# Digital__IO.net
KiCad netlist of a schematic drawn in Altium Designer
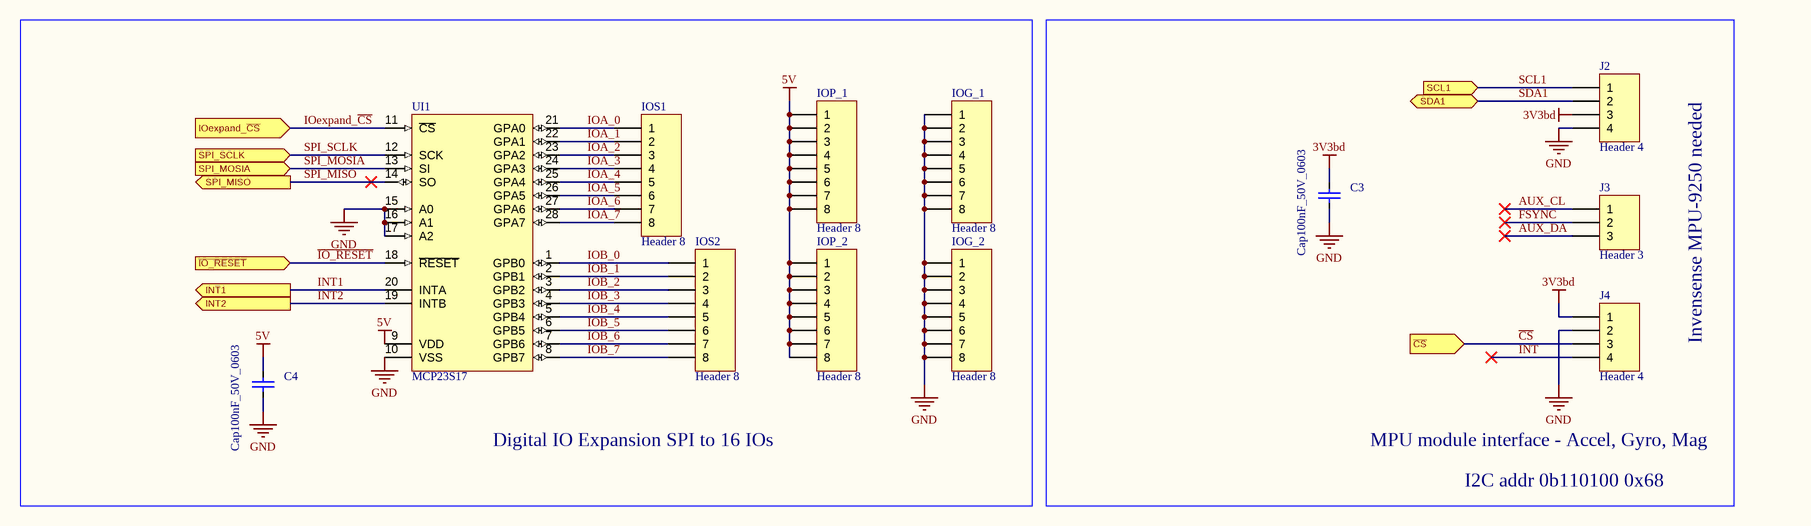
[diagram p0: Digital_ IO.SchDoc]

(export (version "E")
  (design (tool "Eeschema 10.0.6"))
  (components
    (comp (ref "C3")
      (value "Cap100nF_50V_0603")
      (footprint "0603C_L")
      (libsource (lib "Advanced] Training Course - A365") (part "CAP General"))
    )
    (comp (ref "C4")
      (value "Cap100nF_50V_0603")
      (footprint "0603C_L")
      (libsource (lib "Advanced] Training Course - A365") (part "CAP General"))
    )
    (comp (ref "IOG_1")
      (value "Header 8")
      (footprint "HDR1X8")
      (description "Header, 8-Pin")
      (fields (field (name "PUBLISHER") "Altium Limited"))
      (libsource (lib "Advanced] Training Course - A365") (part "Header 8"))
    )
    (comp (ref "IOG_2")
      (value "Header 8")
      (footprint "HDR1X8")
      (description "Header, 8-Pin")
      (fields (field (name "PUBLISHER") "Altium Limited"))
      (libsource (lib "Advanced] Training Course - A365") (part "Header 8"))
    )
    (comp (ref "IOP_1")
      (value "Header 8")
      (footprint "HDR1X8")
      (description "Header, 8-Pin")
      (fields (field (name "PUBLISHER") "Altium Limited"))
      (libsource (lib "Advanced] Training Course - A365") (part "Header 8"))
    )
    (comp (ref "IOP_2")
      (value "Header 8")
      (footprint "HDR1X8")
      (description "Header, 8-Pin")
      (fields (field (name "PUBLISHER") "Altium Limited"))
      (libsource (lib "Advanced] Training Course - A365") (part "Header 8"))
    )
    (comp (ref "IOS1")
      (value "Header 8")
      (footprint "HDR1X8")
      (description "Header, 8-Pin")
      (fields (field (name "PUBLISHER") "Altium Limited"))
      (libsource (lib "Advanced] Training Course - A365") (part "Header 8"))
    )
    (comp (ref "IOS2")
      (value "Header 8")
      (footprint "HDR1X8")
      (description "Header, 8-Pin")
      (fields (field (name "PUBLISHER") "Altium Limited"))
      (libsource (lib "Advanced] Training Course - A365") (part "Header 8"))
    )
    (comp (ref "J2")
      (value "Header 4")
      (footprint "HDR1X4")
      (description "Header, 4-Pin")
      (fields (field (name "PUBLISHER") "Altium Limited"))
      (libsource (lib "Advanced] Training Course - A365") (part "Header 4"))
    )
    (comp (ref "J3")
      (value "Header 3")
      (footprint "HDR1X3")
      (description "Header, 3-Pin")
      (fields (field (name "PUBLISHER") "Altium Limited"))
      (libsource (lib "Advanced] Training Course - A365") (part "Header 3"))
    )
    (comp (ref "J4")
      (value "Header 4")
      (footprint "HDR1X4")
      (description "Header, 4-Pin")
      (fields (field (name "PUBLISHER") "Altium Limited"))
      (libsource (lib "Advanced] Training Course - A365") (part "Header 4"))
    )
    (comp (ref "UI1")
      (value "MCP23S17")
      (footprint "SOIC-SO28_L")
      (description "16-Bit I/O Expander with Serial Interface, 28-Pin SOIC, Extended Temperature, Tape and Reel")
      (fields
        (field (name "MANUFACTURER") "Microchip")
        (field (name "MANUFACTURER PART NUMBER") "MCP23S17T-E/SO")
        (field (name "AVAILABLE PREVIEW IMAGES") "2D")
      )
      (libsource (lib "Advanced] Training Course - A365") (part "MCP23S17"))
    )
  )
  (nets
    (net (code "1") (name "/AUX_CL") (class "Default")
      (node (ref "J3") (pin "1") (pinfunction "1_1") (pintype "passive+no_connect"))
    )
    (net (code "2") (name "/AUX_DA") (class "Default")
      (node (ref "J3") (pin "3") (pinfunction "3_3") (pintype "passive+no_connect"))
    )
    (net (code "3") (name "/FSYNC") (class "Default")
      (node (ref "J3") (pin "2") (pinfunction "2_2") (pintype "passive+no_connect"))
    )
    (net (code "4") (name "/INT") (class "Default")
      (node (ref "J4") (pin "4") (pinfunction "4_4") (pintype "passive+no_connect"))
    )
    (net (code "5") (name "/INT1") (class "Default")
      (node (ref "UI1") (pin "20") (pinfunction "INTA_20") (pintype "open_collector"))
    )
    (net (code "6") (name "/INT2") (class "Default")
      (node (ref "UI1") (pin "19") (pinfunction "INTB_19") (pintype "open_collector"))
    )
    (net (code "7") (name "/IOA_0") (class "Default")
      (node (ref "IOS1") (pin "1") (pinfunction "1_1") (pintype "passive"))
      (node (ref "UI1") (pin "21") (pinfunction "GPA0_21") (pintype "bidirectional"))
    )
    (net (code "8") (name "/IOA_1") (class "Default")
      (node (ref "IOS1") (pin "2") (pinfunction "2_2") (pintype "passive"))
      (node (ref "UI1") (pin "22") (pinfunction "GPA1_22") (pintype "bidirectional"))
    )
    (net (code "9") (name "/IOA_2") (class "Default")
      (node (ref "IOS1") (pin "3") (pinfunction "3_3") (pintype "passive"))
      (node (ref "UI1") (pin "23") (pinfunction "GPA2_23") (pintype "bidirectional"))
    )
    (net (code "10") (name "/IOA_3") (class "Default")
      (node (ref "IOS1") (pin "4") (pinfunction "4_4") (pintype "passive"))
      (node (ref "UI1") (pin "24") (pinfunction "GPA3_24") (pintype "bidirectional"))
    )
    (net (code "11") (name "/IOA_4") (class "Default")
      (node (ref "IOS1") (pin "5") (pinfunction "5_5") (pintype "passive"))
      (node (ref "UI1") (pin "25") (pinfunction "GPA4_25") (pintype "bidirectional"))
    )
    (net (code "12") (name "/IOA_5") (class "Default")
      (node (ref "IOS1") (pin "6") (pinfunction "6_6") (pintype "passive"))
      (node (ref "UI1") (pin "26") (pinfunction "GPA5_26") (pintype "bidirectional"))
    )
    (net (code "13") (name "/IOA_6") (class "Default")
      (node (ref "IOS1") (pin "7") (pinfunction "7_7") (pintype "passive"))
      (node (ref "UI1") (pin "27") (pinfunction "GPA6_27") (pintype "bidirectional"))
    )
    (net (code "14") (name "/IOA_7") (class "Default")
      (node (ref "IOS1") (pin "8") (pinfunction "8_8") (pintype "passive"))
      (node (ref "UI1") (pin "28") (pinfunction "GPA7_28") (pintype "bidirectional"))
    )
    (net (code "15") (name "/IOB_0") (class "Default")
      (node (ref "IOS2") (pin "1") (pinfunction "1_1") (pintype "passive"))
      (node (ref "UI1") (pin "1") (pinfunction "GPB0_1") (pintype "bidirectional"))
    )
    (net (code "16") (name "/IOB_1") (class "Default")
      (node (ref "IOS2") (pin "2") (pinfunction "2_2") (pintype "passive"))
      (node (ref "UI1") (pin "2") (pinfunction "GPB1_2") (pintype "bidirectional"))
    )
    (net (code "17") (name "/IOB_2") (class "Default")
      (node (ref "IOS2") (pin "3") (pinfunction "3_3") (pintype "passive"))
      (node (ref "UI1") (pin "3") (pinfunction "GPB2_3") (pintype "bidirectional"))
    )
    (net (code "18") (name "/IOB_3") (class "Default")
      (node (ref "IOS2") (pin "4") (pinfunction "4_4") (pintype "passive"))
      (node (ref "UI1") (pin "4") (pinfunction "GPB3_4") (pintype "bidirectional"))
    )
    (net (code "19") (name "/IOB_4") (class "Default")
      (node (ref "IOS2") (pin "5") (pinfunction "5_5") (pintype "passive"))
      (node (ref "UI1") (pin "5") (pinfunction "GPB4_5") (pintype "bidirectional"))
    )
    (net (code "20") (name "/IOB_5") (class "Default")
      (node (ref "IOS2") (pin "6") (pinfunction "6_6") (pintype "passive"))
      (node (ref "UI1") (pin "6") (pinfunction "GPB5_6") (pintype "bidirectional"))
    )
    (net (code "21") (name "/IOB_6") (class "Default")
      (node (ref "IOS2") (pin "7") (pinfunction "7_7") (pintype "passive"))
      (node (ref "UI1") (pin "7") (pinfunction "GPB6_7") (pintype "bidirectional"))
    )
    (net (code "22") (name "/IOB_7") (class "Default")
      (node (ref "IOS2") (pin "8") (pinfunction "8_8") (pintype "passive"))
      (node (ref "UI1") (pin "8") (pinfunction "GPB7_8") (pintype "bidirectional"))
    )
    (net (code "23") (name "/IO_RESET") (class "Default")
      (node (ref "UI1") (pin "18") (pinfunction "~{RESET}_18") (pintype "input"))
    )
    (net (code "24") (name "/IOexpand_~{CS}") (class "Default")
      (node (ref "UI1") (pin "11") (pinfunction "~{CS}_11") (pintype "input"))
    )
    (net (code "25") (name "/SCL1") (class "Default")
      (node (ref "J2") (pin "1") (pinfunction "1_1") (pintype "passive"))
    )
    (net (code "26") (name "/SDA1") (class "Default")
      (node (ref "J2") (pin "2") (pinfunction "2_2") (pintype "passive"))
    )
    (net (code "27") (name "/SPI_MISO") (class "Default")
      (node (ref "UI1") (pin "14") (pinfunction "SO_14") (pintype "bidirectional"))
    )
    (net (code "28") (name "/SPI_MOSIA") (class "Default")
      (node (ref "UI1") (pin "13") (pinfunction "SI_13") (pintype "input"))
    )
    (net (code "29") (name "/SPI_SCLK") (class "Default")
      (node (ref "UI1") (pin "12") (pinfunction "SCK_12") (pintype "input"))
    )
    (net (code "30") (name "/~{CS}") (class "Default")
      (node (ref "J4") (pin "3") (pinfunction "3_3") (pintype "passive"))
    )
    (net (code "31") (name "3V3bd") (class "Default")
      (node (ref "C3") (pin "2") (pinfunction "2_2") (pintype "passive"))
      (node (ref "J2") (pin "3") (pinfunction "3_3") (pintype "passive"))
      (node (ref "J4") (pin "1") (pinfunction "1_1") (pintype "passive"))
    )
    (net (code "32") (name "5V") (class "Default")
      (node (ref "C4") (pin "2") (pinfunction "2_2") (pintype "passive"))
      (node (ref "IOP_1") (pin "1") (pinfunction "1_1") (pintype "passive"))
      (node (ref "IOP_1") (pin "2") (pinfunction "2_2") (pintype "passive"))
      (node (ref "IOP_1") (pin "3") (pinfunction "3_3") (pintype "passive"))
      (node (ref "IOP_1") (pin "4") (pinfunction "4_4") (pintype "passive"))
      (node (ref "IOP_1") (pin "5") (pinfunction "5_5") (pintype "passive"))
      (node (ref "IOP_1") (pin "6") (pinfunction "6_6") (pintype "passive"))
      (node (ref "IOP_1") (pin "7") (pinfunction "7_7") (pintype "passive"))
      (node (ref "IOP_1") (pin "8") (pinfunction "8_8") (pintype "passive"))
      (node (ref "IOP_2") (pin "1") (pinfunction "1_1") (pintype "passive"))
      (node (ref "IOP_2") (pin "2") (pinfunction "2_2") (pintype "passive"))
      (node (ref "IOP_2") (pin "3") (pinfunction "3_3") (pintype "passive"))
      (node (ref "IOP_2") (pin "4") (pinfunction "4_4") (pintype "passive"))
      (node (ref "IOP_2") (pin "5") (pinfunction "5_5") (pintype "passive"))
      (node (ref "IOP_2") (pin "6") (pinfunction "6_6") (pintype "passive"))
      (node (ref "IOP_2") (pin "7") (pinfunction "7_7") (pintype "passive"))
      (node (ref "IOP_2") (pin "8") (pinfunction "8_8") (pintype "passive"))
      (node (ref "UI1") (pin "9") (pinfunction "VDD_9") (pintype "power_in"))
    )
    (net (code "33") (name "GND") (class "Default")
      (node (ref "C3") (pin "1") (pinfunction "1_1") (pintype "passive"))
      (node (ref "C4") (pin "1") (pinfunction "1_1") (pintype "passive"))
      (node (ref "IOG_1") (pin "1") (pinfunction "1_1") (pintype "passive"))
      (node (ref "IOG_1") (pin "2") (pinfunction "2_2") (pintype "passive"))
      (node (ref "IOG_1") (pin "3") (pinfunction "3_3") (pintype "passive"))
      (node (ref "IOG_1") (pin "4") (pinfunction "4_4") (pintype "passive"))
      (node (ref "IOG_1") (pin "5") (pinfunction "5_5") (pintype "passive"))
      (node (ref "IOG_1") (pin "6") (pinfunction "6_6") (pintype "passive"))
      (node (ref "IOG_1") (pin "7") (pinfunction "7_7") (pintype "passive"))
      (node (ref "IOG_1") (pin "8") (pinfunction "8_8") (pintype "passive"))
      (node (ref "IOG_2") (pin "1") (pinfunction "1_1") (pintype "passive"))
      (node (ref "IOG_2") (pin "2") (pinfunction "2_2") (pintype "passive"))
      (node (ref "IOG_2") (pin "3") (pinfunction "3_3") (pintype "passive"))
      (node (ref "IOG_2") (pin "4") (pinfunction "4_4") (pintype "passive"))
      (node (ref "IOG_2") (pin "5") (pinfunction "5_5") (pintype "passive"))
      (node (ref "IOG_2") (pin "6") (pinfunction "6_6") (pintype "passive"))
      (node (ref "IOG_2") (pin "7") (pinfunction "7_7") (pintype "passive"))
      (node (ref "IOG_2") (pin "8") (pinfunction "8_8") (pintype "passive"))
      (node (ref "J2") (pin "4") (pinfunction "4_4") (pintype "passive"))
      (node (ref "J4") (pin "2") (pinfunction "2_2") (pintype "passive"))
      (node (ref "UI1") (pin "10") (pinfunction "VSS_10") (pintype "power_in"))
      (node (ref "UI1") (pin "15") (pinfunction "A0_15") (pintype "input"))
      (node (ref "UI1") (pin "16") (pinfunction "A1_16") (pintype "input"))
      (node (ref "UI1") (pin "17") (pinfunction "A2_17") (pintype "input"))
    )
  )
)
